# untitled.net
KiCad netlist of a schematic drawn in EAGLE
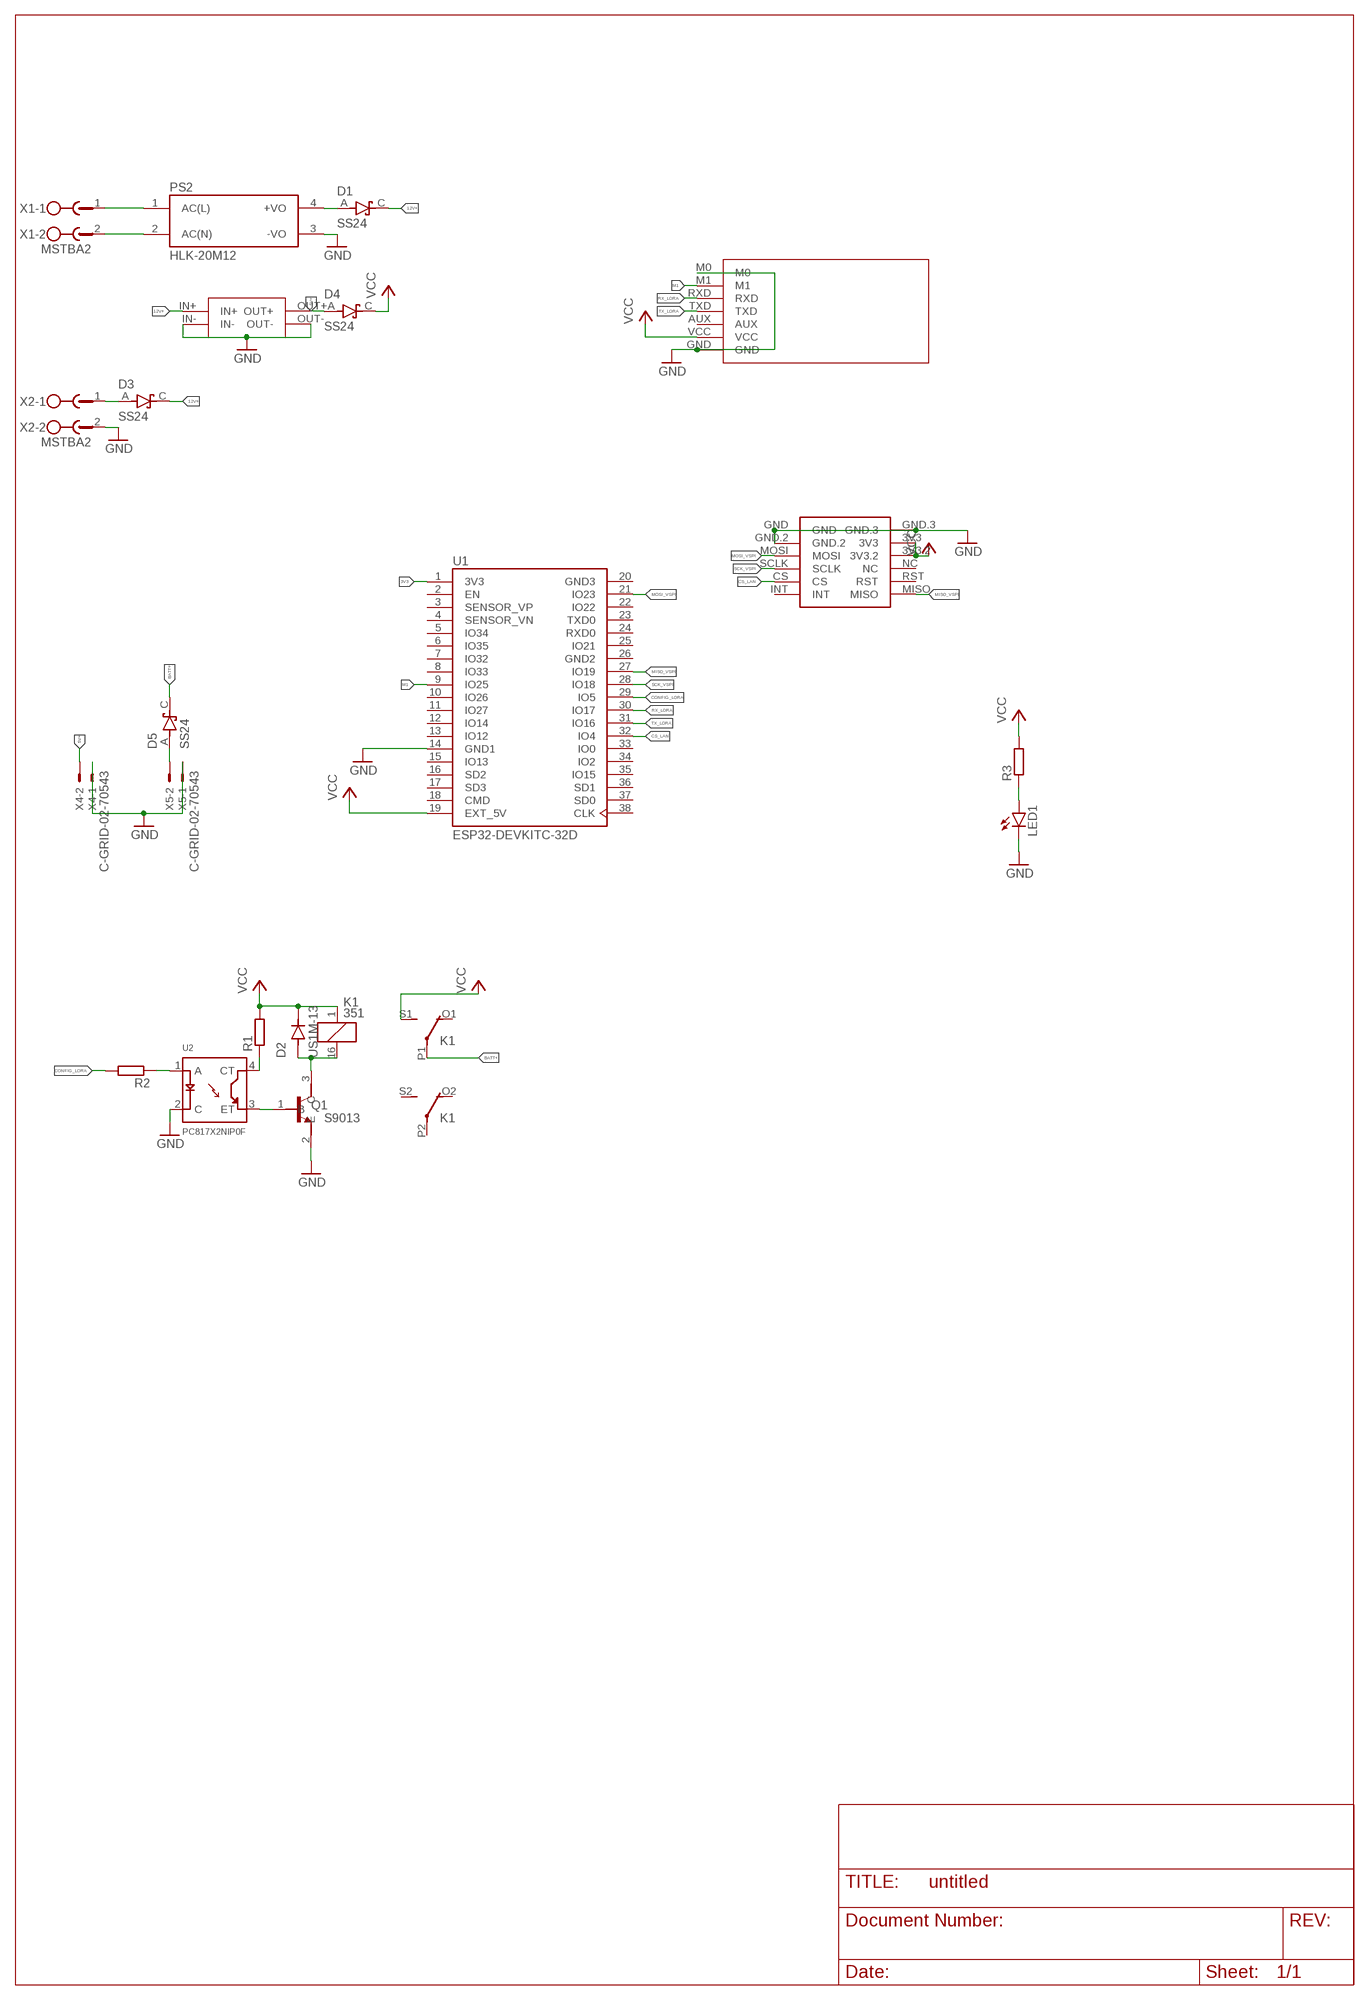
[diagram p0: schematic, sheet 1]

(export (version "E")
  (design (tool "Eeschema 10.0.6"))
  (components
    (comp (ref "D1")
      (value "SS24")
      (footprint "eagle-import:DIOM5336X265N")
      (fields (field (name "MF") "ON Semiconductor"))
      (libsource (lib "eagle-import") (part "SS24"))
    )
    (comp (ref "D2")
      (value "US1M-13")
      (footprint "eagle-import:DIOM5226X240N")
      (fields (field (name "MF") "Diodes Incorporated"))
      (libsource (lib "eagle-import") (part "US1M-13"))
    )
    (comp (ref "D3")
      (value "SS24")
      (footprint "eagle-import:DIOM5336X265N")
      (fields (field (name "MF") "ON Semiconductor"))
      (libsource (lib "eagle-import") (part "SS24"))
    )
    (comp (ref "D4")
      (value "SS24")
      (footprint "eagle-import:DIOM5336X265N")
      (fields (field (name "MF") "ON Semiconductor"))
      (libsource (lib "eagle-import") (part "SS24"))
    )
    (comp (ref "D5")
      (value "SS24")
      (footprint "eagle-import:DIOM5336X265N")
      (fields (field (name "MF") "ON Semiconductor"))
      (libsource (lib "eagle-import") (part "SS24"))
    )
    (comp (ref "EBYTEE220-900T22D1")
      (value "EBYTEE220-900T22D")
      (footprint "eagle-import:EBYTEE220-900T22D")
      (libsource (lib "eagle-import") (part "EBYTEE220-900T22D"))
    )
    (comp (ref "K1")
      (value "351")
      (footprint "eagle-import:351")
      (libsource (lib "eagle-import") (part "351"))
    )
    (comp (ref "LED1")
      (value "TLLY4400")
      (footprint "eagle-import:LED3MM")
      (fields (field (name "MF") "VISHAY SEMICONDUCTOR"))
      (libsource (lib "eagle-import") (part "TLLY4400"))
    )
    (comp (ref "MINI1")
      (value "MINI560")
      (footprint "eagle-import:MINI560")
      (libsource (lib "eagle-import") (part "MINI560"))
    )
    (comp (ref "PS2")
      (value "HLK-20M12")
      (footprint "eagle-import:CONV_HLK-20M12")
      (fields (field (name "MF") "Hi-link"))
      (libsource (lib "eagle-import") (part "HLK-20M12"))
    )
    (comp (ref "Q1")
      (value "S9013")
      (footprint "eagle-import:SOT95P240X120-3N")
      (fields (field (name "MF") "JCET"))
      (libsource (lib "eagle-import") (part "S9013"))
    )
    (comp (ref "R1")
      (value "R-EU_R0805")
      (footprint "eagle-import:R0805")
      (libsource (lib "eagle-import") (part "R-EU_R0805"))
    )
    (comp (ref "R2")
      (value "R-EU_R0805")
      (footprint "eagle-import:R0805")
      (libsource (lib "eagle-import") (part "R-EU_R0805"))
    )
    (comp (ref "R3")
      (value "R-EU_R0805")
      (footprint "eagle-import:R0805")
      (libsource (lib "eagle-import") (part "R-EU_R0805"))
    )
    (comp (ref "U$1")
      (value "MINI_W5500")
      (footprint "eagle-import:MINI_W5500")
      (libsource (lib "eagle-import") (part "MINI_W5500"))
    )
    (comp (ref "U1")
      (value "ESP32-DEVKITC-32D")
      (footprint "eagle-import:MODULE_ESP32-DEVKITC-32D")
      (fields (field (name "MF") "Espressif Systems"))
      (libsource (lib "eagle-import") (part "ESP32-DEVKITC-32D"))
    )
    (comp (ref "U2")
      (value "PC817X2NIP0F")
      (footprint "eagle-import:SOT254P975X400-4N")
      (fields (field (name "MF") "Sharp Microelectronics"))
      (libsource (lib "eagle-import") (part "PC817X2NIP0F"))
    )
    (comp (ref "X1")
      (value "MSTBA2")
      (footprint "eagle-import:MSTBA2")
      (fields (field (name "MF") "FARNELL") (field (name "MPN") "1757242"))
      (libsource (lib "eagle-import") (part "MSTBA2"))
    )
    (comp (ref "X2")
      (value "MSTBA2")
      (footprint "eagle-import:MSTBA2")
      (fields (field (name "MF") "FARNELL") (field (name "MPN") "1757242"))
      (libsource (lib "eagle-import") (part "MSTBA2"))
    )
    (comp (ref "X4")
      (value "C-GRID-02-70543")
      (footprint "eagle-import:70543-02")
      (fields (field (name "MF") "MOLEX"))
      (libsource (lib "eagle-import") (part "C-GRID-02-70543"))
    )
    (comp (ref "X5")
      (value "C-GRID-02-70543")
      (footprint "eagle-import:70543-02")
      (fields (field (name "MF") "MOLEX"))
      (libsource (lib "eagle-import") (part "C-GRID-02-70543"))
    )
  )
  (nets
    (net (code "1") (name "/GND2") (class "Default")
      (node (ref "U1") (pin "26") (pinfunction "GND2_26") (pintype "power_in"))
    )
    (net (code "2") (name "/GND3") (class "Default")
      (node (ref "U1") (pin "20") (pinfunction "GND3_20") (pintype "power_in"))
    )
    (net (code "3") (name "3V3") (class "Default")
      (node (ref "U1") (pin "1") (pinfunction "3V3_1") (pintype "power_in"))
    )
    (net (code "4") (name "5V+") (class "Default")
      (node (ref "D4") (pin "A") (pinfunction "A_A") (pintype "passive"))
      (node (ref "MINI1") (pin "OUT+") (pinfunction "OUT+_OUT+") (pintype "bidirectional"))
      (node (ref "X4") (pin "2") (pinfunction "S_2") (pintype "passive"))
    )
    (net (code "5") (name "12V+") (class "Default")
      (node (ref "D1") (pin "C") (pinfunction "K_C") (pintype "passive"))
      (node (ref "D3") (pin "C") (pinfunction "K_C") (pintype "passive"))
      (node (ref "MINI1") (pin "IN+") (pinfunction "IN+_IN+") (pintype "bidirectional"))
    )
    (net (code "6") (name "BATT+") (class "Default")
      (node (ref "D5") (pin "C") (pinfunction "K_C") (pintype "passive"))
      (node (ref "K1") (pin "P1") (pinfunction "P_P1") (pintype "passive"))
    )
    (net (code "7") (name "CONFIG_LORA") (class "Default")
      (node (ref "R2") (pin "2") (pinfunction "2_2") (pintype "passive"))
      (node (ref "U1") (pin "29") (pinfunction "IO5_29") (pintype "bidirectional"))
    )
    (net (code "8") (name "CS_LAN") (class "Default")
      (node (ref "U$1") (pin "CS") (pinfunction "CS_CS") (pintype "bidirectional"))
      (node (ref "U1") (pin "32") (pinfunction "IO4_32") (pintype "bidirectional"))
    )
    (net (code "9") (name "GND") (class "Default")
      (node (ref "EBYTEE220-900T22D1") (pin "GND") (pinfunction "GND_GND") (pintype "bidirectional"))
      (node (ref "EBYTEE220-900T22D1") (pin "M0") (pinfunction "M0_M0") (pintype "bidirectional"))
      (node (ref "LED1") (pin "K") (pinfunction "C_K") (pintype "passive"))
      (node (ref "MINI1") (pin "IN-") (pinfunction "IN-_IN-") (pintype "bidirectional"))
      (node (ref "MINI1") (pin "OUT-") (pinfunction "OUT-_OUT-") (pintype "bidirectional"))
      (node (ref "PS2") (pin "3") (pinfunction "-VO_3") (pintype "output"))
      (node (ref "Q1") (pin "2") (pinfunction "E_2") (pintype "passive"))
      (node (ref "U$1") (pin "GND") (pinfunction "GND_GND") (pintype "bidirectional"))
      (node (ref "U$1") (pin "GND.2") (pinfunction "GND.2_GND.2") (pintype "bidirectional"))
      (node (ref "U$1") (pin "GND.3") (pinfunction "GND.3_GND.3") (pintype "bidirectional"))
      (node (ref "U1") (pin "14") (pinfunction "GND1_14") (pintype "power_in"))
      (node (ref "U2") (pin "2") (pinfunction "C_2") (pintype "passive"))
      (node (ref "X2") (pin "2") (pinfunction "1_2") (pintype "passive"))
      (node (ref "X4") (pin "1") (pinfunction "S_1") (pintype "passive"))
      (node (ref "X5") (pin "1") (pinfunction "S_1") (pintype "passive"))
    )
    (net (code "10") (name "M1") (class "Default")
      (node (ref "EBYTEE220-900T22D1") (pin "M1") (pinfunction "M1_M1") (pintype "bidirectional"))
      (node (ref "U1") (pin "9") (pinfunction "IO25_9") (pintype "bidirectional"))
    )
    (net (code "11") (name "MISO_VSPI") (class "Default")
      (node (ref "U$1") (pin "MISO") (pinfunction "MISO_MISO") (pintype "bidirectional"))
      (node (ref "U1") (pin "27") (pinfunction "IO19_27") (pintype "bidirectional"))
    )
    (net (code "12") (name "MOSI_VSPI") (class "Default")
      (node (ref "U$1") (pin "MOSI") (pinfunction "MOSI_MOSI") (pintype "bidirectional"))
      (node (ref "U1") (pin "21") (pinfunction "IO23_21") (pintype "bidirectional"))
    )
    (net (code "13") (name "Net-(D3-PadA)") (class "Default")
      (node (ref "D3") (pin "A") (pinfunction "A_A") (pintype "passive"))
      (node (ref "X2") (pin "1") (pinfunction "1_1") (pintype "passive"))
    )
    (net (code "14") (name "Net-(K1A-2)") (class "Default")
      (node (ref "D2") (pin "A") (pinfunction "A_A") (pintype "passive"))
      (node (ref "K1") (pin "16") (pinfunction "2_16") (pintype "passive"))
      (node (ref "Q1") (pin "3") (pinfunction "C_3") (pintype "passive"))
    )
    (net (code "15") (name "Net-(LED1-PadA)") (class "Default")
      (node (ref "LED1") (pin "A") (pinfunction "A_A") (pintype "passive"))
      (node (ref "R3") (pin "1") (pinfunction "1_1") (pintype "passive"))
    )
    (net (code "16") (name "Net-(PS2-+VO)") (class "Default")
      (node (ref "D1") (pin "A") (pinfunction "A_A") (pintype "passive"))
      (node (ref "PS2") (pin "4") (pinfunction "+VO_4") (pintype "output"))
    )
    (net (code "17") (name "Net-(PS2-AC(L))") (class "Default")
      (node (ref "PS2") (pin "1") (pinfunction "AC(L)_1") (pintype "input"))
      (node (ref "X1") (pin "1") (pinfunction "1_1") (pintype "passive"))
    )
    (net (code "18") (name "Net-(PS2-AC(N))") (class "Default")
      (node (ref "PS2") (pin "2") (pinfunction "AC(N)_2") (pintype "input"))
      (node (ref "X1") (pin "2") (pinfunction "1_2") (pintype "passive"))
    )
    (net (code "19") (name "Net-(Q1-B)") (class "Default")
      (node (ref "Q1") (pin "1") (pinfunction "B_1") (pintype "passive"))
      (node (ref "U2") (pin "3") (pinfunction "ET_3") (pintype "passive"))
    )
    (net (code "20") (name "Net-(U2-A)") (class "Default")
      (node (ref "R2") (pin "1") (pinfunction "1_1") (pintype "passive"))
      (node (ref "U2") (pin "1") (pinfunction "A_1") (pintype "passive"))
    )
    (net (code "21") (name "Net-(U2-CT)") (class "Default")
      (node (ref "R1") (pin "1") (pinfunction "1_1") (pintype "passive"))
      (node (ref "U2") (pin "4") (pinfunction "CT_4") (pintype "passive"))
    )
    (net (code "22") (name "Net-(X5B-S)") (class "Default")
      (node (ref "D5") (pin "A") (pinfunction "A_A") (pintype "passive"))
      (node (ref "X5") (pin "2") (pinfunction "S_2") (pintype "passive"))
    )
    (net (code "23") (name "RX_LORA") (class "Default")
      (node (ref "EBYTEE220-900T22D1") (pin "RXD") (pinfunction "RXD_RXD") (pintype "bidirectional"))
      (node (ref "U1") (pin "30") (pinfunction "IO17_30") (pintype "bidirectional"))
    )
    (net (code "24") (name "SCK_VSPI") (class "Default")
      (node (ref "U$1") (pin "SCLK") (pinfunction "SCLK_SCLK") (pintype "bidirectional"))
      (node (ref "U1") (pin "28") (pinfunction "IO18_28") (pintype "bidirectional"))
    )
    (net (code "25") (name "TX_LORA") (class "Default")
      (node (ref "EBYTEE220-900T22D1") (pin "TXD") (pinfunction "TXD_TXD") (pintype "bidirectional"))
      (node (ref "U1") (pin "31") (pinfunction "IO16_31") (pintype "bidirectional"))
    )
    (net (code "26") (name "VCC") (class "Default")
      (node (ref "D2") (pin "C") (pinfunction "K_C") (pintype "passive"))
      (node (ref "D4") (pin "C") (pinfunction "K_C") (pintype "passive"))
      (node (ref "EBYTEE220-900T22D1") (pin "VCC") (pinfunction "VCC_VCC") (pintype "bidirectional"))
      (node (ref "K1") (pin "1") (pinfunction "1_1") (pintype "passive"))
      (node (ref "K1") (pin "S1") (pinfunction "S_S1") (pintype "passive"))
      (node (ref "R1") (pin "2") (pinfunction "2_2") (pintype "passive"))
      (node (ref "R3") (pin "2") (pinfunction "2_2") (pintype "passive"))
      (node (ref "U$1") (pin "3V3") (pinfunction "3V3_3V3") (pintype "bidirectional"))
      (node (ref "U$1") (pin "3V3.2") (pinfunction "3V3.2_3V3.2") (pintype "bidirectional"))
      (node (ref "U1") (pin "19") (pinfunction "EXT_5V_19") (pintype "power_in"))
    )
    (net (code "27") (name "unconnected-(EBYTEE220-900T22D1-PadAUX)") (class "Default")
      (node (ref "EBYTEE220-900T22D1") (pin "AUX") (pinfunction "AUX_AUX") (pintype "bidirectional"))
    )
    (net (code "28") (name "unconnected-(K1B-O-PadO1)") (class "Default")
      (node (ref "K1") (pin "O1") (pinfunction "O_O1") (pintype "passive"))
    )
    (net (code "29") (name "unconnected-(K1C-O-PadO2)") (class "Default")
      (node (ref "K1") (pin "O2") (pinfunction "O_O2") (pintype "passive"))
    )
    (net (code "30") (name "unconnected-(K1C-P-PadP2)") (class "Default")
      (node (ref "K1") (pin "P2") (pinfunction "P_P2") (pintype "passive"))
    )
    (net (code "31") (name "unconnected-(K1C-S-PadS2)") (class "Default")
      (node (ref "K1") (pin "S2") (pinfunction "S_S2") (pintype "passive"))
    )
    (net (code "32") (name "unconnected-(U$1-PadINT)") (class "Default")
      (node (ref "U$1") (pin "INT") (pinfunction "INT_INT") (pintype "bidirectional"))
    )
    (net (code "33") (name "unconnected-(U$1-PadNC)") (class "Default")
      (node (ref "U$1") (pin "NC") (pinfunction "NC_NC") (pintype "bidirectional"))
    )
    (net (code "34") (name "unconnected-(U$1-PadRST)") (class "Default")
      (node (ref "U$1") (pin "RST") (pinfunction "RST_RST") (pintype "bidirectional"))
    )
    (net (code "35") (name "unconnected-(U1-CLK-Pad38)") (class "Default")
      (node (ref "U1") (pin "38") (pinfunction "CLK_38") (pintype "input"))
    )
    (net (code "36") (name "unconnected-(U1-CMD-Pad18)") (class "Default")
      (node (ref "U1") (pin "18") (pinfunction "CMD_18") (pintype "bidirectional"))
    )
    (net (code "37") (name "unconnected-(U1-EN-Pad2)") (class "Default")
      (node (ref "U1") (pin "2") (pinfunction "EN_2") (pintype "input"))
    )
    (net (code "38") (name "unconnected-(U1-IO0-Pad33)") (class "Default")
      (node (ref "U1") (pin "33") (pinfunction "IO0_33") (pintype "bidirectional"))
    )
    (net (code "39") (name "unconnected-(U1-IO2-Pad34)") (class "Default")
      (node (ref "U1") (pin "34") (pinfunction "IO2_34") (pintype "bidirectional"))
    )
    (net (code "40") (name "unconnected-(U1-IO12-Pad13)") (class "Default")
      (node (ref "U1") (pin "13") (pinfunction "IO12_13") (pintype "bidirectional"))
    )
    (net (code "41") (name "unconnected-(U1-IO13-Pad15)") (class "Default")
      (node (ref "U1") (pin "15") (pinfunction "IO13_15") (pintype "bidirectional"))
    )
    (net (code "42") (name "unconnected-(U1-IO14-Pad12)") (class "Default")
      (node (ref "U1") (pin "12") (pinfunction "IO14_12") (pintype "bidirectional"))
    )
    (net (code "43") (name "unconnected-(U1-IO15-Pad35)") (class "Default")
      (node (ref "U1") (pin "35") (pinfunction "IO15_35") (pintype "bidirectional"))
    )
    (net (code "44") (name "unconnected-(U1-IO21-Pad25)") (class "Default")
      (node (ref "U1") (pin "25") (pinfunction "IO21_25") (pintype "bidirectional"))
    )
    (net (code "45") (name "unconnected-(U1-IO22-Pad22)") (class "Default")
      (node (ref "U1") (pin "22") (pinfunction "IO22_22") (pintype "bidirectional"))
    )
    (net (code "46") (name "unconnected-(U1-IO26-Pad10)") (class "Default")
      (node (ref "U1") (pin "10") (pinfunction "IO26_10") (pintype "bidirectional"))
    )
    (net (code "47") (name "unconnected-(U1-IO27-Pad11)") (class "Default")
      (node (ref "U1") (pin "11") (pinfunction "IO27_11") (pintype "bidirectional"))
    )
    (net (code "48") (name "unconnected-(U1-IO32-Pad7)") (class "Default")
      (node (ref "U1") (pin "7") (pinfunction "IO32_7") (pintype "bidirectional"))
    )
    (net (code "49") (name "unconnected-(U1-IO33-Pad8)") (class "Default")
      (node (ref "U1") (pin "8") (pinfunction "IO33_8") (pintype "bidirectional"))
    )
    (net (code "50") (name "unconnected-(U1-IO34-Pad5)") (class "Default")
      (node (ref "U1") (pin "5") (pinfunction "IO34_5") (pintype "bidirectional"))
    )
    (net (code "51") (name "unconnected-(U1-IO35-Pad6)") (class "Default")
      (node (ref "U1") (pin "6") (pinfunction "IO35_6") (pintype "bidirectional"))
    )
    (net (code "52") (name "unconnected-(U1-RXD0-Pad24)") (class "Default")
      (node (ref "U1") (pin "24") (pinfunction "RXD0_24") (pintype "input"))
    )
    (net (code "53") (name "unconnected-(U1-SD0-Pad37)") (class "Default")
      (node (ref "U1") (pin "37") (pinfunction "SD0_37") (pintype "bidirectional"))
    )
    (net (code "54") (name "unconnected-(U1-SD1-Pad36)") (class "Default")
      (node (ref "U1") (pin "36") (pinfunction "SD1_36") (pintype "bidirectional"))
    )
    (net (code "55") (name "unconnected-(U1-SD2-Pad16)") (class "Default")
      (node (ref "U1") (pin "16") (pinfunction "SD2_16") (pintype "bidirectional"))
    )
    (net (code "56") (name "unconnected-(U1-SD3-Pad17)") (class "Default")
      (node (ref "U1") (pin "17") (pinfunction "SD3_17") (pintype "bidirectional"))
    )
    (net (code "57") (name "unconnected-(U1-SENSOR_VN-Pad4)") (class "Default")
      (node (ref "U1") (pin "4") (pinfunction "SENSOR_VN_4") (pintype "input"))
    )
    (net (code "58") (name "unconnected-(U1-SENSOR_VP-Pad3)") (class "Default")
      (node (ref "U1") (pin "3") (pinfunction "SENSOR_VP_3") (pintype "input"))
    )
    (net (code "59") (name "unconnected-(U1-TXD0-Pad23)") (class "Default")
      (node (ref "U1") (pin "23") (pinfunction "TXD0_23") (pintype "output"))
    )
  )
)
